# Umb104.net
KiCad netlist of a schematic drawn in Altium Designer
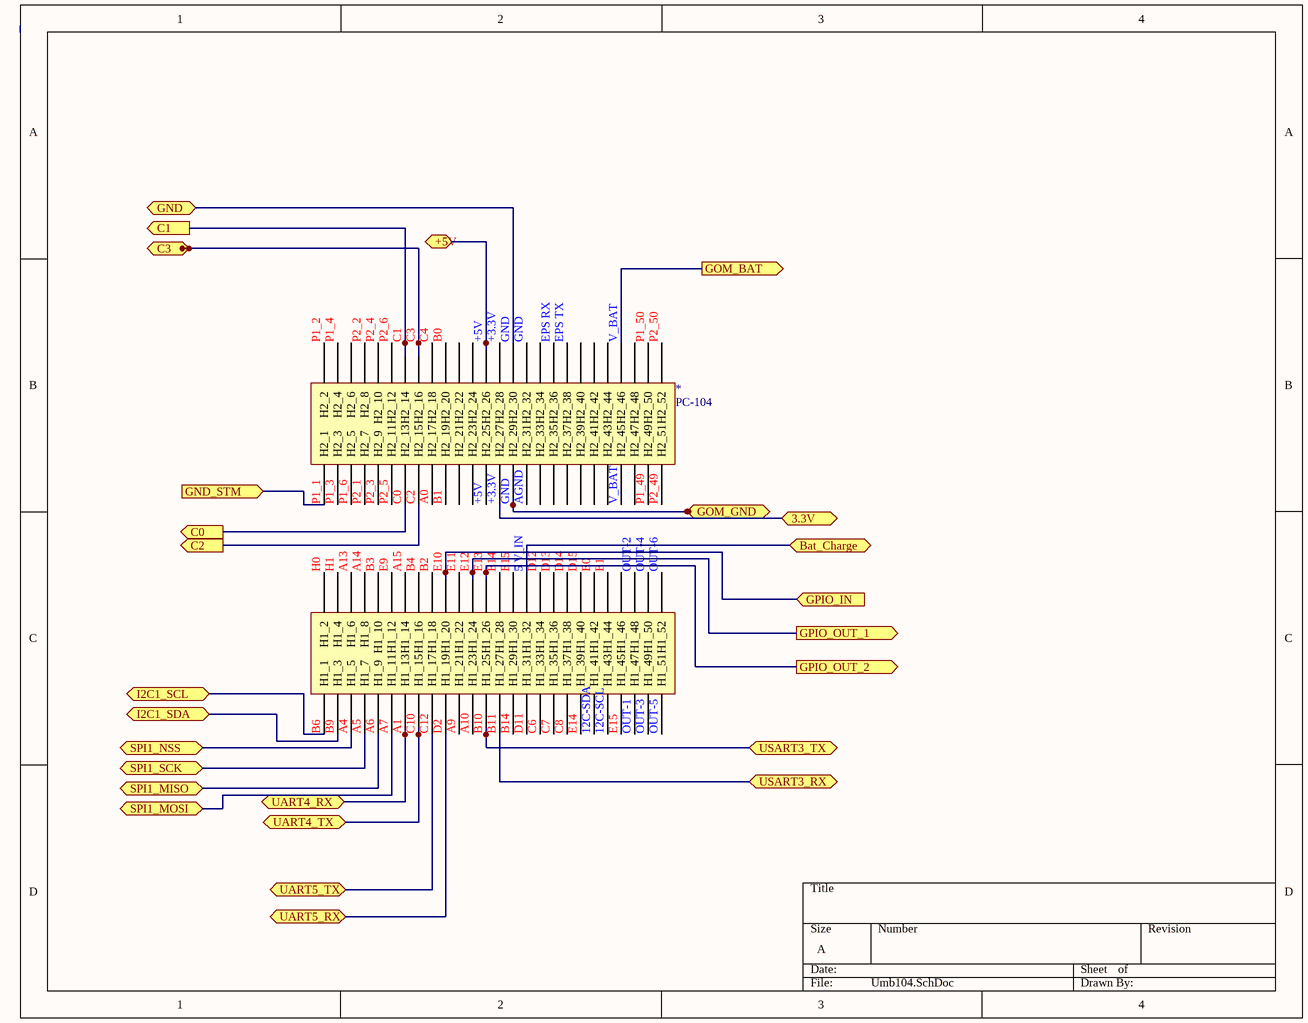
[diagram p0: Umb104.SchDoc]

(export (version "E")
  (design (tool "Eeschema 10.0.6"))
  (components
    (comp (ref "*")
      (value "PC-104")
      (footprint "PC-104FOOTPRINT")
      (libsource (lib "AdapterBoard") (part "PC-104"))
    )
  )
  (nets
    (net (code "1") (name "/+3.3V") (class "Default")
      (node (ref "*") (pin "H2_27") (pinfunction "H2_27_H2_27") (pintype "passive"))
      (node (ref "*") (pin "H2_28") (pinfunction "H2_28_H2_28") (pintype "passive"))
    )
    (net (code "2") (name "/+5V") (class "Default")
      (node (ref "*") (pin "H2_25") (pinfunction "H2_25_H2_25") (pintype "passive"))
      (node (ref "*") (pin "H2_26") (pinfunction "H2_26_H2_26") (pintype "passive"))
    )
    (net (code "3") (name "/5 V_IN") (class "Default")
      (node (ref "*") (pin "H1_32") (pinfunction "H1_32_H1_32") (pintype "passive"))
    )
    (net (code "4") (name "/12C-SCL") (class "Default")
      (node (ref "*") (pin "H1_43") (pinfunction "H1_43_H1_43") (pintype "passive"))
    )
    (net (code "5") (name "/12C-SDA") (class "Default")
      (node (ref "*") (pin "H1_41") (pinfunction "H1_41_H1_41") (pintype "passive"))
    )
    (net (code "6") (name "/A0") (class "Default")
      (node (ref "*") (pin "H2_17") (pinfunction "H2_17_H2_17") (pintype "passive"))
    )
    (net (code "7") (name "/A1") (class "Default")
      (node (ref "*") (pin "H1_13") (pinfunction "H1_13_H1_13") (pintype "passive"))
    )
    (net (code "8") (name "/A4") (class "Default")
      (node (ref "*") (pin "H1_5") (pinfunction "H1_5_H1_5") (pintype "passive"))
    )
    (net (code "9") (name "/A5") (class "Default")
      (node (ref "*") (pin "H1_7") (pinfunction "H1_7_H1_7") (pintype "passive"))
    )
    (net (code "10") (name "/A6") (class "Default")
      (node (ref "*") (pin "H1_9") (pinfunction "H1_9_H1_9") (pintype "passive"))
    )
    (net (code "11") (name "/A7") (class "Default")
      (node (ref "*") (pin "H1_11") (pinfunction "H1_11_H1_11") (pintype "passive"))
    )
    (net (code "12") (name "/A9") (class "Default")
      (node (ref "*") (pin "H1_21") (pinfunction "H1_21_H1_21") (pintype "passive"))
    )
    (net (code "13") (name "/A10") (class "Default")
      (node (ref "*") (pin "H1_23") (pinfunction "H1_23_H1_23") (pintype "passive"))
    )
    (net (code "14") (name "/A13") (class "Default")
      (node (ref "*") (pin "H1_6") (pinfunction "H1_6_H1_6") (pintype "passive"))
    )
    (net (code "15") (name "/A14") (class "Default")
      (node (ref "*") (pin "H1_8") (pinfunction "H1_8_H1_8") (pintype "passive"))
    )
    (net (code "16") (name "/A15") (class "Default")
      (node (ref "*") (pin "H1_14") (pinfunction "H1_14_H1_14") (pintype "passive"))
    )
    (net (code "17") (name "/AGND") (class "Default")
      (node (ref "*") (pin "H2_31") (pinfunction "H2_31_H2_31") (pintype "passive"))
    )
    (net (code "18") (name "/B0") (class "Default")
      (node (ref "*") (pin "H2_20") (pinfunction "H2_20_H2_20") (pintype "passive"))
    )
    (net (code "19") (name "/B1") (class "Default")
      (node (ref "*") (pin "H2_19") (pinfunction "H2_19_H2_19") (pintype "passive"))
    )
    (net (code "20") (name "/B2") (class "Default")
      (node (ref "*") (pin "H1_18") (pinfunction "H1_18_H1_18") (pintype "passive"))
    )
    (net (code "21") (name "/B3") (class "Default")
      (node (ref "*") (pin "H1_10") (pinfunction "H1_10_H1_10") (pintype "passive"))
    )
    (net (code "22") (name "/B4") (class "Default")
      (node (ref "*") (pin "H1_16") (pinfunction "H1_16_H1_16") (pintype "passive"))
    )
    (net (code "23") (name "/B6") (class "Default")
      (node (ref "*") (pin "H1_1") (pinfunction "H1_1_H1_1") (pintype "passive"))
    )
    (net (code "24") (name "/B9") (class "Default")
      (node (ref "*") (pin "H1_3") (pinfunction "H1_3_H1_3") (pintype "passive"))
    )
    (net (code "25") (name "/B10") (class "Default")
      (node (ref "*") (pin "H1_25") (pinfunction "H1_25_H1_25") (pintype "passive"))
    )
    (net (code "26") (name "/B11") (class "Default")
      (node (ref "*") (pin "H1_27") (pinfunction "H1_27_H1_27") (pintype "passive"))
    )
    (net (code "27") (name "/B14") (class "Default")
      (node (ref "*") (pin "H1_29") (pinfunction "H1_29_H1_29") (pintype "passive"))
    )
    (net (code "28") (name "/C0") (class "Default")
      (node (ref "*") (pin "H2_13") (pinfunction "H2_13_H2_13") (pintype "passive"))
    )
    (net (code "29") (name "/C1") (class "Default")
      (node (ref "*") (pin "H2_14") (pinfunction "H2_14_H2_14") (pintype "passive"))
    )
    (net (code "30") (name "/C2") (class "Default")
      (node (ref "*") (pin "H2_15") (pinfunction "H2_15_H2_15") (pintype "passive"))
    )
    (net (code "31") (name "/C3") (class "Default")
      (node (ref "*") (pin "H2_16") (pinfunction "H2_16_H2_16") (pintype "passive"))
    )
    (net (code "32") (name "/C4") (class "Default")
      (node (ref "*") (pin "H2_18") (pinfunction "H2_18_H2_18") (pintype "passive"))
    )
    (net (code "33") (name "/C6") (class "Default")
      (node (ref "*") (pin "H1_33") (pinfunction "H1_33_H1_33") (pintype "passive"))
    )
    (net (code "34") (name "/C7") (class "Default")
      (node (ref "*") (pin "H1_35") (pinfunction "H1_35_H1_35") (pintype "passive"))
    )
    (net (code "35") (name "/C8") (class "Default")
      (node (ref "*") (pin "H1_37") (pinfunction "H1_37_H1_37") (pintype "passive"))
    )
    (net (code "36") (name "/C10") (class "Default")
      (node (ref "*") (pin "H1_15") (pinfunction "H1_15_H1_15") (pintype "passive"))
    )
    (net (code "37") (name "/C12") (class "Default")
      (node (ref "*") (pin "H1_17") (pinfunction "H1_17_H1_17") (pintype "passive"))
    )
    (net (code "38") (name "/D2") (class "Default")
      (node (ref "*") (pin "H1_19") (pinfunction "H1_19_H1_19") (pintype "passive"))
    )
    (net (code "39") (name "/D11") (class "Default")
      (node (ref "*") (pin "H1_31") (pinfunction "H1_31_H1_31") (pintype "passive"))
    )
    (net (code "40") (name "/D12") (class "Default")
      (node (ref "*") (pin "H1_34") (pinfunction "H1_34_H1_34") (pintype "passive"))
    )
    (net (code "41") (name "/D13") (class "Default")
      (node (ref "*") (pin "H1_36") (pinfunction "H1_36_H1_36") (pintype "passive"))
    )
    (net (code "42") (name "/D14") (class "Default")
      (node (ref "*") (pin "H1_38") (pinfunction "H1_38_H1_38") (pintype "passive"))
    )
    (net (code "43") (name "/D15") (class "Default")
      (node (ref "*") (pin "H1_40") (pinfunction "H1_40_H1_40") (pintype "passive"))
    )
    (net (code "44") (name "/E0") (class "Default")
      (node (ref "*") (pin "H1_42") (pinfunction "H1_42_H1_42") (pintype "passive"))
    )
    (net (code "45") (name "/E1") (class "Default")
      (node (ref "*") (pin "H1_44") (pinfunction "H1_44_H1_44") (pintype "passive"))
    )
    (net (code "46") (name "/E9") (class "Default")
      (node (ref "*") (pin "H1_12") (pinfunction "H1_12_H1_12") (pintype "passive"))
    )
    (net (code "47") (name "/E10") (class "Default")
      (node (ref "*") (pin "H1_20") (pinfunction "H1_20_H1_20") (pintype "passive"))
    )
    (net (code "48") (name "/E11") (class "Default")
      (node (ref "*") (pin "H1_22") (pinfunction "H1_22_H1_22") (pintype "passive"))
    )
    (net (code "49") (name "/E12") (class "Default")
      (node (ref "*") (pin "H1_24") (pinfunction "H1_24_H1_24") (pintype "passive"))
    )
    (net (code "50") (name "/E13") (class "Default")
      (node (ref "*") (pin "H1_26") (pinfunction "H1_26_H1_26") (pintype "passive"))
    )
    (net (code "51") (name "/E14") (class "Default")
      (node (ref "*") (pin "H1_28") (pinfunction "H1_28_H1_28") (pintype "passive"))
      (node (ref "*") (pin "H1_39") (pinfunction "H1_39_H1_39") (pintype "passive"))
    )
    (net (code "52") (name "/E15") (class "Default")
      (node (ref "*") (pin "H1_30") (pinfunction "H1_30_H1_30") (pintype "passive"))
      (node (ref "*") (pin "H1_45") (pinfunction "H1_45_H1_45") (pintype "passive"))
    )
    (net (code "53") (name "/EPS RX") (class "Default")
      (node (ref "*") (pin "H2_36") (pinfunction "H2_36_H2_36") (pintype "passive"))
    )
    (net (code "54") (name "/EPS TX") (class "Default")
      (node (ref "*") (pin "H2_38") (pinfunction "H2_38_H2_38") (pintype "passive"))
    )
    (net (code "55") (name "/GND") (class "Default")
      (node (ref "*") (pin "H2_29") (pinfunction "H2_29_H2_29") (pintype "passive"))
      (node (ref "*") (pin "H2_30") (pinfunction "H2_30_H2_30") (pintype "passive"))
      (node (ref "*") (pin "H2_32") (pinfunction "H2_32_H2_32") (pintype "passive"))
    )
    (net (code "56") (name "/H0") (class "Default")
      (node (ref "*") (pin "H1_2") (pinfunction "H1_2_H1_2") (pintype "passive"))
    )
    (net (code "57") (name "/H1") (class "Default")
      (node (ref "*") (pin "H1_4") (pinfunction "H1_4_H1_4") (pintype "passive"))
    )
    (net (code "58") (name "/OUT-1") (class "Default")
      (node (ref "*") (pin "H1_47") (pinfunction "H1_47_H1_47") (pintype "passive"))
    )
    (net (code "59") (name "/OUT-2") (class "Default")
      (node (ref "*") (pin "H1_48") (pinfunction "H1_48_H1_48") (pintype "passive"))
    )
    (net (code "60") (name "/OUT-3") (class "Default")
      (node (ref "*") (pin "H1_49") (pinfunction "H1_49_H1_49") (pintype "passive"))
    )
    (net (code "61") (name "/OUT-4") (class "Default")
      (node (ref "*") (pin "H1_50") (pinfunction "H1_50_H1_50") (pintype "passive"))
    )
    (net (code "62") (name "/OUT-5") (class "Default")
      (node (ref "*") (pin "H1_51") (pinfunction "H1_51_H1_51") (pintype "passive"))
    )
    (net (code "63") (name "/OUT-6") (class "Default")
      (node (ref "*") (pin "H1_52") (pinfunction "H1_52_H1_52") (pintype "passive"))
    )
    (net (code "64") (name "/P1_1") (class "Default")
      (node (ref "*") (pin "H2_1") (pinfunction "H2_1_H2_1") (pintype "passive"))
    )
    (net (code "65") (name "/P1_2") (class "Default")
      (node (ref "*") (pin "H2_2") (pinfunction "H2_2_H2_2") (pintype "passive"))
    )
    (net (code "66") (name "/P1_3") (class "Default")
      (node (ref "*") (pin "H2_3") (pinfunction "H2_3_H2_3") (pintype "passive"))
    )
    (net (code "67") (name "/P1_4") (class "Default")
      (node (ref "*") (pin "H2_4") (pinfunction "H2_4_H2_4") (pintype "passive"))
    )
    (net (code "68") (name "/P1_6") (class "Default")
      (node (ref "*") (pin "H2_5") (pinfunction "H2_5_H2_5") (pintype "passive"))
    )
    (net (code "69") (name "/P1_49") (class "Default")
      (node (ref "*") (pin "H2_49") (pinfunction "H2_49_H2_49") (pintype "passive"))
    )
    (net (code "70") (name "/P1_50") (class "Default")
      (node (ref "*") (pin "H2_50") (pinfunction "H2_50_H2_50") (pintype "passive"))
    )
    (net (code "71") (name "/P2_1") (class "Default")
      (node (ref "*") (pin "H2_7") (pinfunction "H2_7_H2_7") (pintype "passive"))
    )
    (net (code "72") (name "/P2_2") (class "Default")
      (node (ref "*") (pin "H2_8") (pinfunction "H2_8_H2_8") (pintype "passive"))
    )
    (net (code "73") (name "/P2_3") (class "Default")
      (node (ref "*") (pin "H2_9") (pinfunction "H2_9_H2_9") (pintype "passive"))
    )
    (net (code "74") (name "/P2_4") (class "Default")
      (node (ref "*") (pin "H2_10") (pinfunction "H2_10_H2_10") (pintype "passive"))
    )
    (net (code "75") (name "/P2_5") (class "Default")
      (node (ref "*") (pin "H2_11") (pinfunction "H2_11_H2_11") (pintype "passive"))
    )
    (net (code "76") (name "/P2_6") (class "Default")
      (node (ref "*") (pin "H2_12") (pinfunction "H2_12_H2_12") (pintype "passive"))
    )
    (net (code "77") (name "/P2_49") (class "Default")
      (node (ref "*") (pin "H2_51") (pinfunction "H2_51_H2_51") (pintype "passive"))
    )
    (net (code "78") (name "/P2_50") (class "Default")
      (node (ref "*") (pin "H2_52") (pinfunction "H2_52_H2_52") (pintype "passive"))
    )
    (net (code "79") (name "/V_BAT") (class "Default")
      (node (ref "*") (pin "H2_45") (pinfunction "H2_45_H2_45") (pintype "passive"))
      (node (ref "*") (pin "H2_46") (pinfunction "H2_46_H2_46") (pintype "passive"))
    )
    (net (code "80") (name "unconnected-(*-PadH1_46)") (class "Default")
      (node (ref "*") (pin "H1_46") (pinfunction "H1_46_H1_46") (pintype "passive"))
    )
    (net (code "81") (name "unconnected-(*-PadH2_6)") (class "Default")
      (node (ref "*") (pin "H2_6") (pinfunction "H2_6_H2_6") (pintype "passive"))
    )
    (net (code "82") (name "unconnected-(*-PadH2_21)") (class "Default")
      (node (ref "*") (pin "H2_21") (pinfunction "H2_21_H2_21") (pintype "passive"))
    )
    (net (code "83") (name "unconnected-(*-PadH2_22)") (class "Default")
      (node (ref "*") (pin "H2_22") (pinfunction "H2_22_H2_22") (pintype "passive"))
    )
    (net (code "84") (name "unconnected-(*-PadH2_23)") (class "Default")
      (node (ref "*") (pin "H2_23") (pinfunction "H2_23_H2_23") (pintype "passive"))
    )
    (net (code "85") (name "unconnected-(*-PadH2_24)") (class "Default")
      (node (ref "*") (pin "H2_24") (pinfunction "H2_24_H2_24") (pintype "passive"))
    )
    (net (code "86") (name "unconnected-(*-PadH2_33)") (class "Default")
      (node (ref "*") (pin "H2_33") (pinfunction "H2_33_H2_33") (pintype "passive"))
    )
    (net (code "87") (name "unconnected-(*-PadH2_34)") (class "Default")
      (node (ref "*") (pin "H2_34") (pinfunction "H2_34_H2_34") (pintype "passive"))
    )
    (net (code "88") (name "unconnected-(*-PadH2_35)") (class "Default")
      (node (ref "*") (pin "H2_35") (pinfunction "H2_35_H2_35") (pintype "passive"))
    )
    (net (code "89") (name "unconnected-(*-PadH2_37)") (class "Default")
      (node (ref "*") (pin "H2_37") (pinfunction "H2_37_H2_37") (pintype "passive"))
    )
    (net (code "90") (name "unconnected-(*-PadH2_39)") (class "Default")
      (node (ref "*") (pin "H2_39") (pinfunction "H2_39_H2_39") (pintype "passive"))
    )
    (net (code "91") (name "unconnected-(*-PadH2_40)") (class "Default")
      (node (ref "*") (pin "H2_40") (pinfunction "H2_40_H2_40") (pintype "passive"))
    )
    (net (code "92") (name "unconnected-(*-PadH2_41)") (class "Default")
      (node (ref "*") (pin "H2_41") (pinfunction "H2_41_H2_41") (pintype "passive"))
    )
    (net (code "93") (name "unconnected-(*-PadH2_42)") (class "Default")
      (node (ref "*") (pin "H2_42") (pinfunction "H2_42_H2_42") (pintype "passive"))
    )
    (net (code "94") (name "unconnected-(*-PadH2_43)") (class "Default")
      (node (ref "*") (pin "H2_43") (pinfunction "H2_43_H2_43") (pintype "passive"))
    )
    (net (code "95") (name "unconnected-(*-PadH2_44)") (class "Default")
      (node (ref "*") (pin "H2_44") (pinfunction "H2_44_H2_44") (pintype "passive"))
    )
    (net (code "96") (name "unconnected-(*-PadH2_47)") (class "Default")
      (node (ref "*") (pin "H2_47") (pinfunction "H2_47_H2_47") (pintype "passive"))
    )
    (net (code "97") (name "unconnected-(*-PadH2_48)") (class "Default")
      (node (ref "*") (pin "H2_48") (pinfunction "H2_48_H2_48") (pintype "passive"))
    )
  )
)
